# 4_Channel_Relay_Board_Omron.net
KiCad netlist of a schematic drawn in EasyEDA
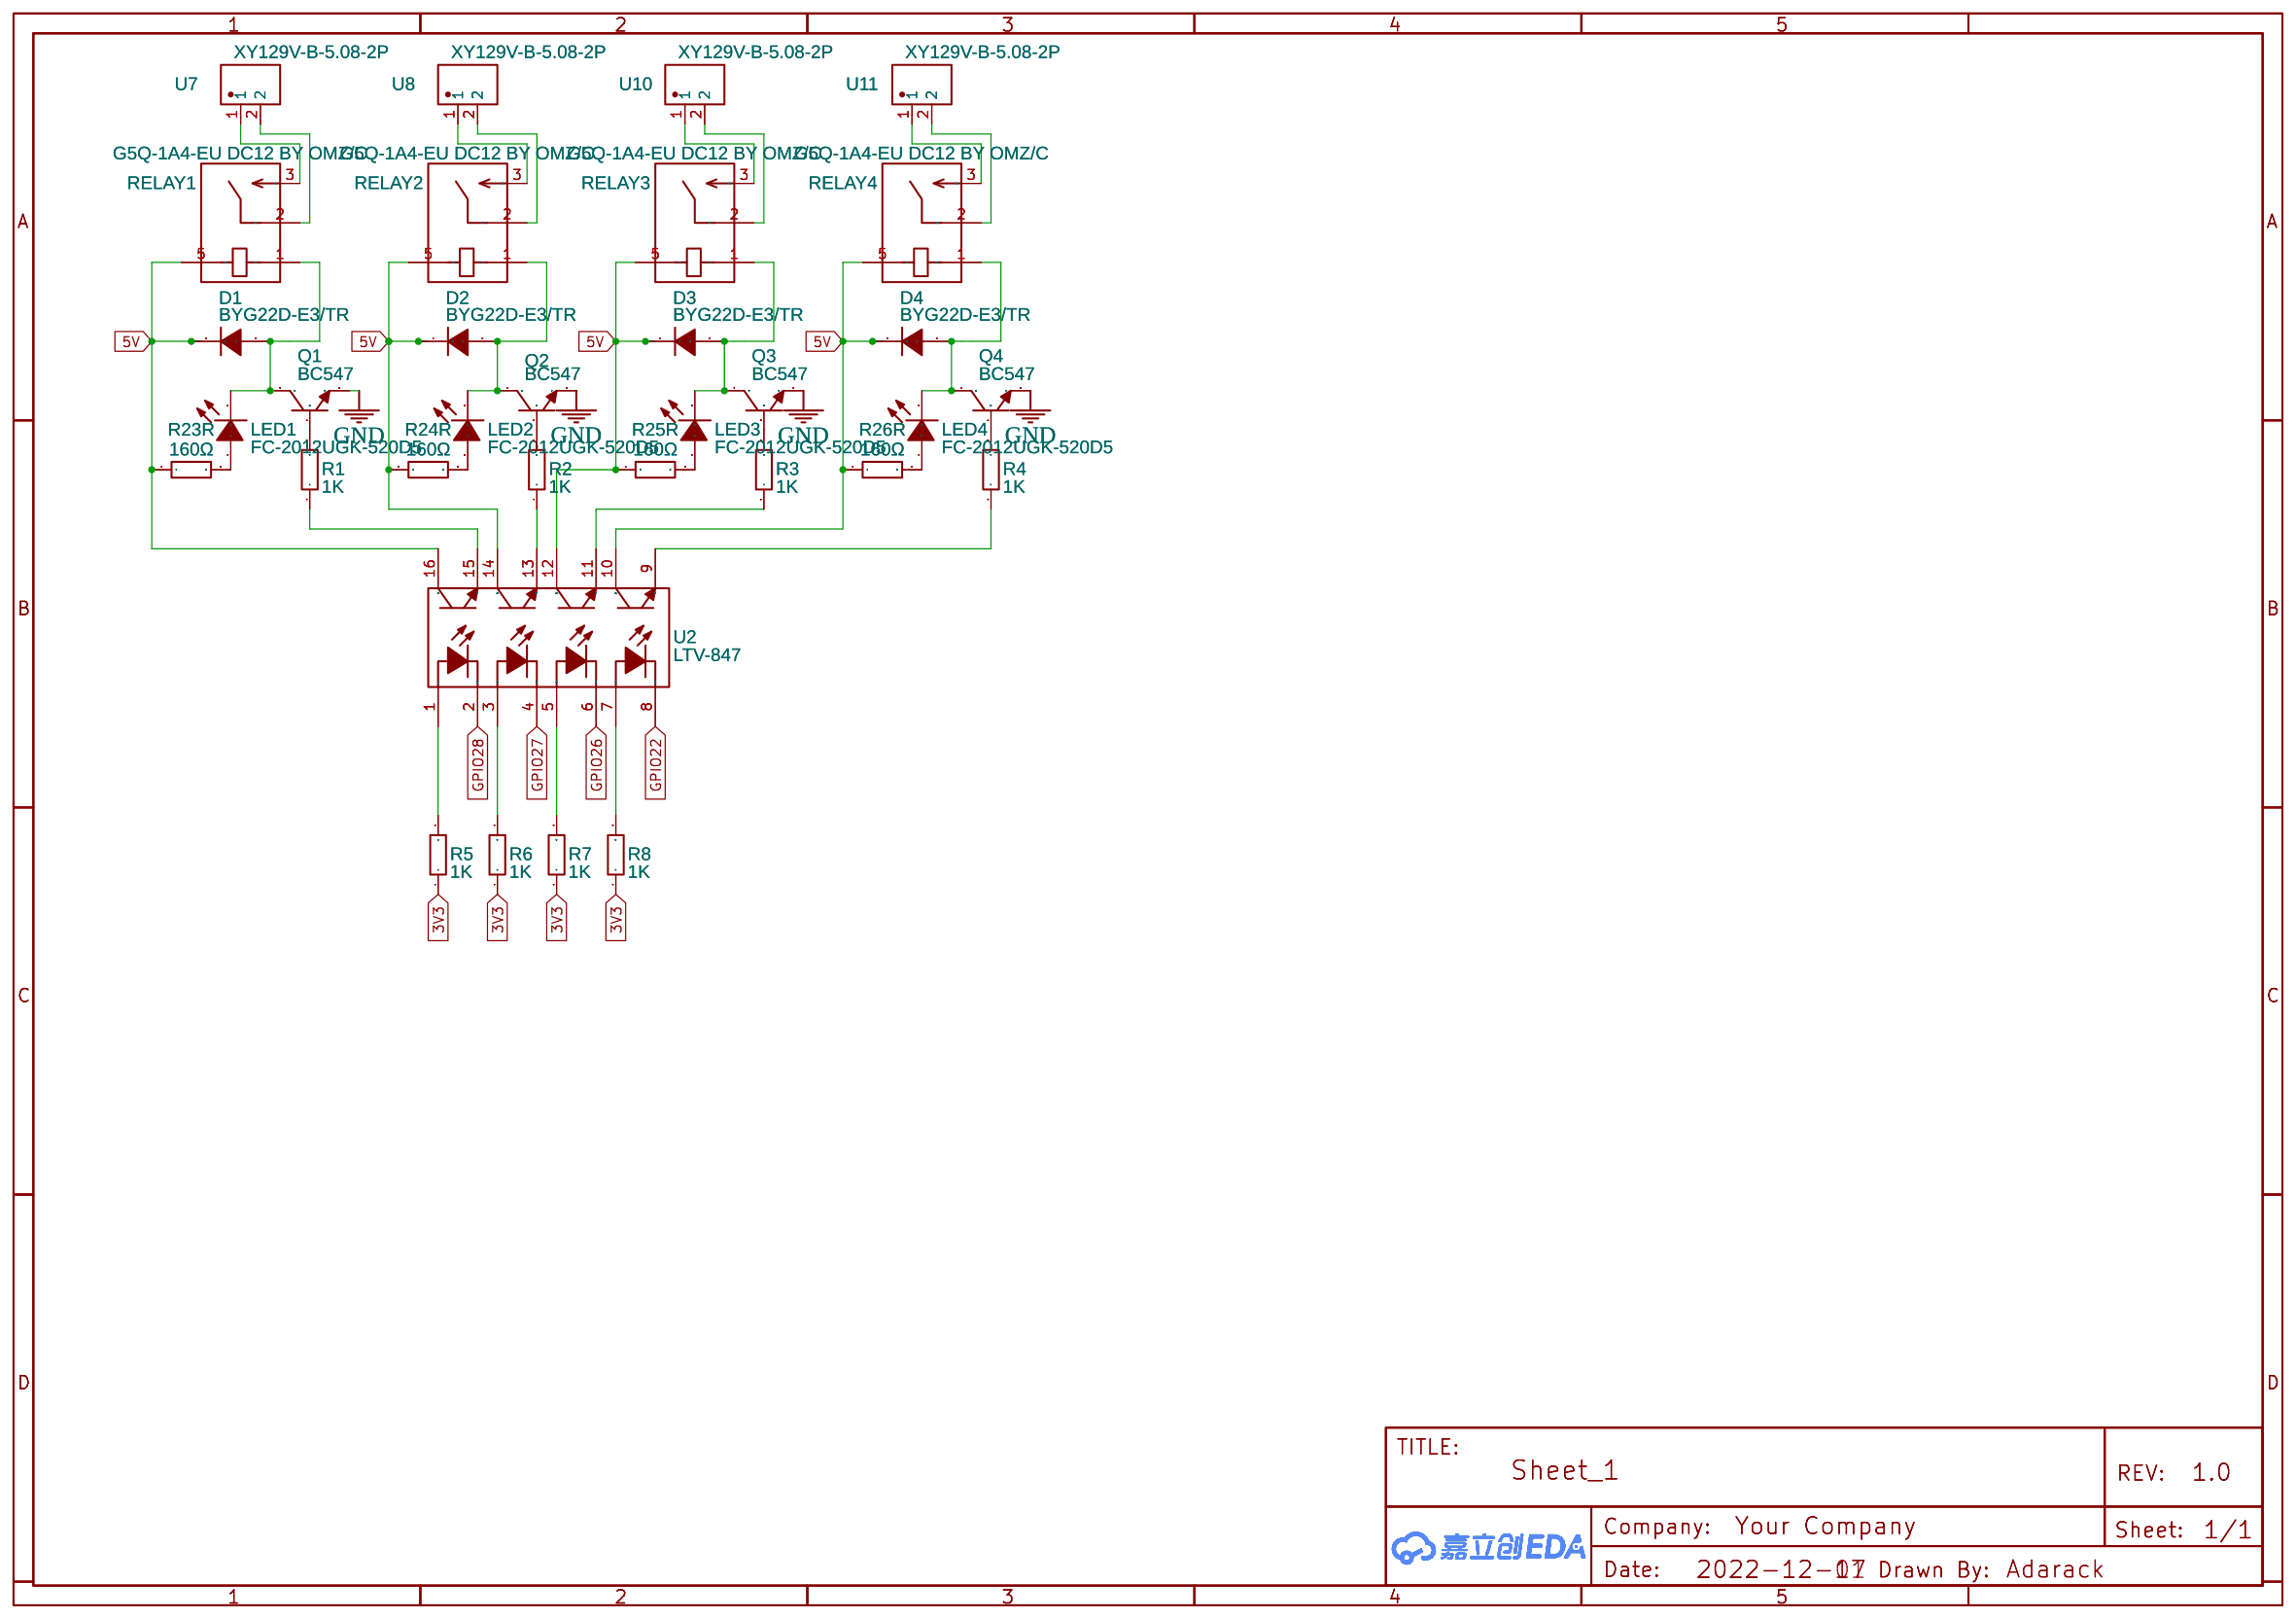
[diagram p0: Relay Section copy]
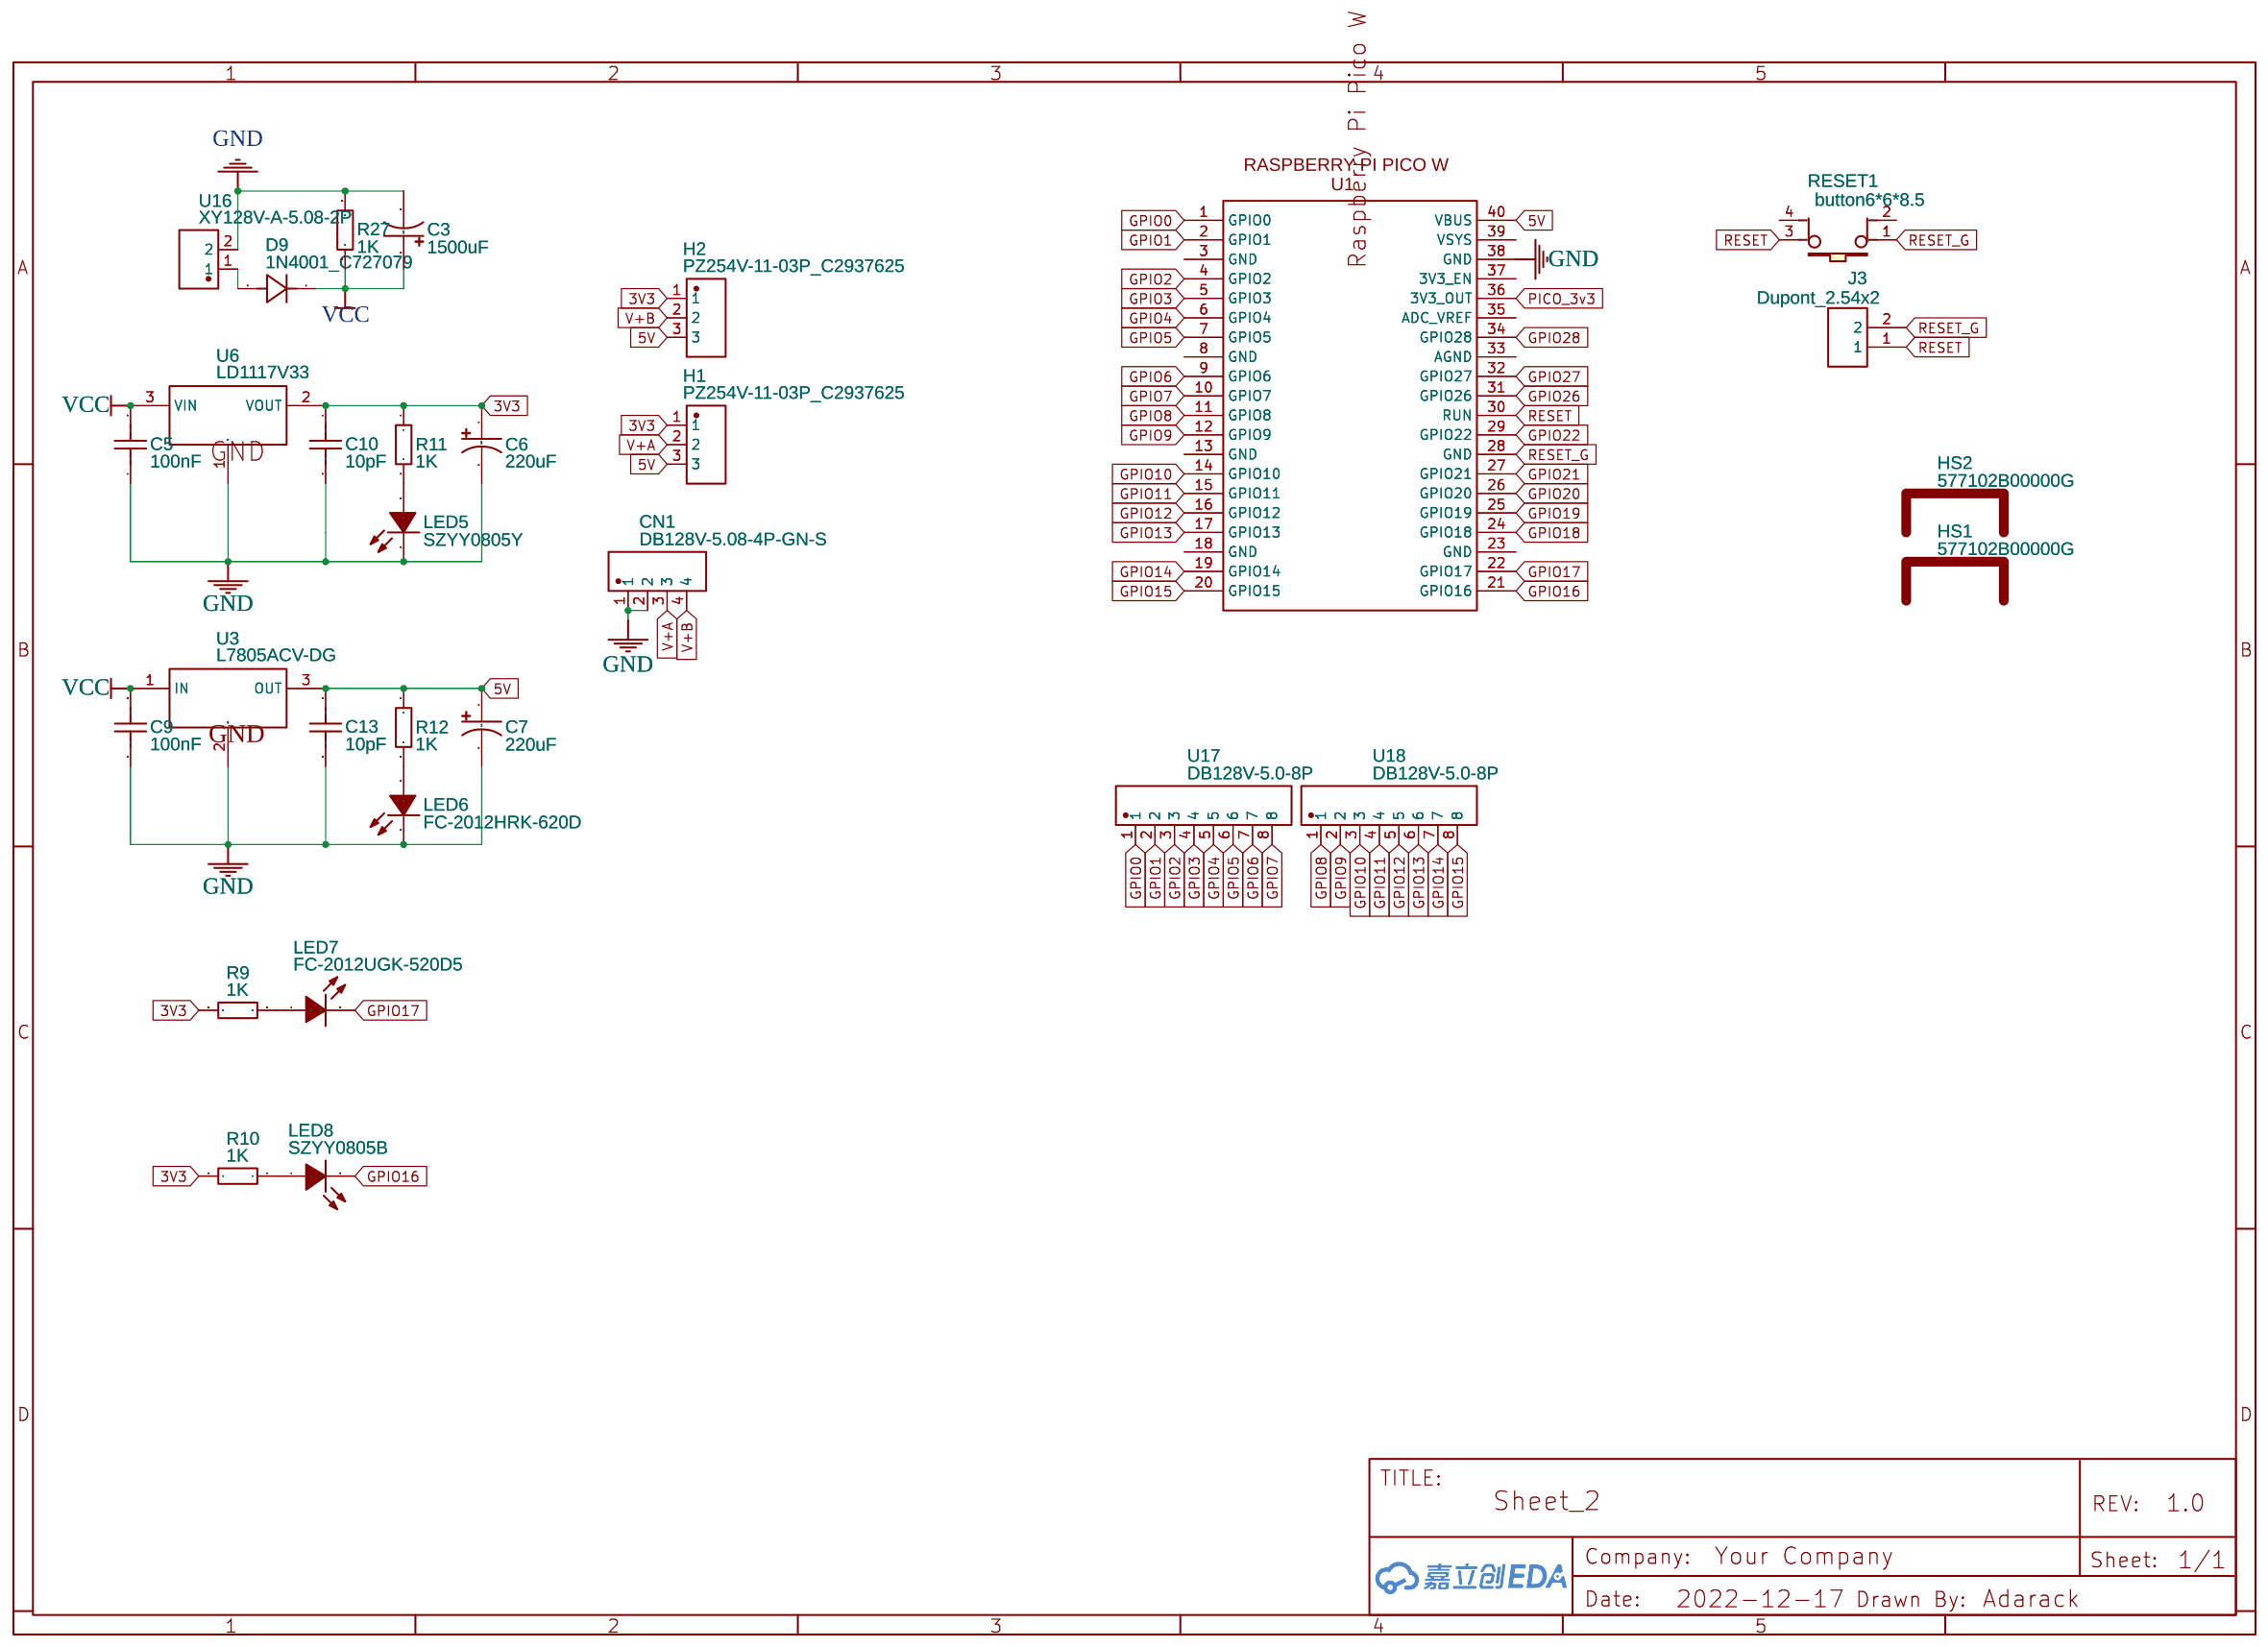
[diagram p1: Pico W Section copy]

(export (version "E")
  (design (tool "Eeschema 10.0.6"))
  (components
    (comp (ref "D1")
      (value "BYG22D-E3/TR")
      (fields (field (name "BOM_Supplier Part") "C52782"))
      (libsource (lib "") (part "BYG22D-E3/TR"))
    )
    (comp (ref "D2")
      (value "BYG22D-E3/TR")
      (fields (field (name "BOM_Supplier Part") "C52782"))
      (libsource (lib "") (part "BYG22D-E3/TR"))
    )
    (comp (ref "D3")
      (value "BYG22D-E3/TR")
      (fields (field (name "BOM_Supplier Part") "C52782"))
      (libsource (lib "") (part "BYG22D-E3/TR"))
    )
    (comp (ref "D4")
      (value "BYG22D-E3/TR")
      (fields (field (name "BOM_Supplier Part") "C52782"))
      (libsource (lib "") (part "BYG22D-E3/TR"))
    )
    (comp (ref "LED1")
      (value "FC-2012UGK-520D5")
      (fields (field (name "BOM_Manufacturer Part") "NCD0805G1") (field (name "BOM_Supplier Part") "C84260"))
      (libsource (lib "") (part "FC-2012UGK-520D5"))
    )
    (comp (ref "LED2")
      (value "FC-2012UGK-520D5")
      (fields (field (name "BOM_Manufacturer Part") "NCD0805G1") (field (name "BOM_Supplier Part") "C84260"))
      (libsource (lib "") (part "FC-2012UGK-520D5"))
    )
    (comp (ref "LED3")
      (value "FC-2012UGK-520D5")
      (fields (field (name "BOM_Manufacturer Part") "NCD0805G1") (field (name "BOM_Supplier Part") "C84260"))
      (libsource (lib "") (part "FC-2012UGK-520D5"))
    )
    (comp (ref "LED4")
      (value "FC-2012UGK-520D5")
      (fields (field (name "BOM_Manufacturer Part") "NCD0805G1") (field (name "BOM_Supplier Part") "C84260"))
      (libsource (lib "") (part "FC-2012UGK-520D5"))
    )
    (comp (ref "Q1")
      (value "BC547")
      (fields (field (name "BOM_Supplier Part") "C2910381"))
      (libsource (lib "") (part "BC547"))
    )
    (comp (ref "Q2")
      (value "BC547")
      (fields (field (name "BOM_Supplier Part") "C2910381"))
      (libsource (lib "") (part "BC547"))
    )
    (comp (ref "Q3")
      (value "BC547")
      (fields (field (name "BOM_Supplier Part") "C2910381"))
      (libsource (lib "") (part "BC547"))
    )
    (comp (ref "Q4")
      (value "BC547")
      (fields (field (name "BOM_Supplier Part") "C2910381"))
      (libsource (lib "") (part "BC547"))
    )
    (comp (ref "R1")
      (value "1K")
      (fields
        (field (name "BOM_Manufacturer Part") "RC0805FR-071KL")
        (field (name "BOM_Supplier Part") "C95781")
      )
      (libsource (lib "") (part "RC0805FR-071KL"))
    )
    (comp (ref "R2")
      (value "1K")
      (fields
        (field (name "BOM_Manufacturer Part") "RC0805FR-071KL")
        (field (name "BOM_Supplier Part") "C95781")
      )
      (libsource (lib "") (part "RC0805FR-071KL"))
    )
    (comp (ref "R3")
      (value "1K")
      (fields
        (field (name "BOM_Manufacturer Part") "RC0805FR-071KL")
        (field (name "BOM_Supplier Part") "C95781")
      )
      (libsource (lib "") (part "RC0805FR-071KL"))
    )
    (comp (ref "R4")
      (value "1K")
      (fields
        (field (name "BOM_Manufacturer Part") "RC0805FR-071KL")
        (field (name "BOM_Supplier Part") "C95781")
      )
      (libsource (lib "") (part "RC0805FR-071KL"))
    )
    (comp (ref "R5")
      (value "1K")
      (fields
        (field (name "BOM_Manufacturer Part") "RC0805FR-071KL")
        (field (name "BOM_Supplier Part") "C95781")
      )
      (libsource (lib "") (part "RC0805FR-071KL"))
    )
    (comp (ref "R6")
      (value "1K")
      (fields
        (field (name "BOM_Manufacturer Part") "RC0805FR-071KL")
        (field (name "BOM_Supplier Part") "C95781")
      )
      (libsource (lib "") (part "RC0805FR-071KL"))
    )
    (comp (ref "R7")
      (value "1K")
      (fields
        (field (name "BOM_Manufacturer Part") "RC0805FR-071KL")
        (field (name "BOM_Supplier Part") "C95781")
      )
      (libsource (lib "") (part "RC0805FR-071KL"))
    )
    (comp (ref "R8")
      (value "1K")
      (fields
        (field (name "BOM_Manufacturer Part") "RC0805FR-071KL")
        (field (name "BOM_Supplier Part") "C95781")
      )
      (libsource (lib "") (part "RC0805FR-071KL"))
    )
    (comp (ref "R23R")
      (value "160Ω")
      (fields
        (field (name "BOM_Manufacturer Part") "0805W8F1600T5E")
        (field (name "BOM_Supplier Part") "C25269")
      )
      (libsource (lib "") (part "0805W8F1600T5E"))
    )
    (comp (ref "R24R")
      (value "160Ω")
      (fields
        (field (name "BOM_Manufacturer Part") "0805W8F1600T5E")
        (field (name "BOM_Supplier Part") "C25269")
      )
      (libsource (lib "") (part "0805W8F1600T5E_1"))
    )
    (comp (ref "R25R")
      (value "160Ω")
      (fields
        (field (name "BOM_Manufacturer Part") "0805W8F1600T5E")
        (field (name "BOM_Supplier Part") "C25269")
      )
      (libsource (lib "") (part "0805W8F1600T5E_3"))
    )
    (comp (ref "R26R")
      (value "160Ω")
      (fields
        (field (name "BOM_Manufacturer Part") "0805W8F1600T5E")
        (field (name "BOM_Supplier Part") "C25269")
      )
      (libsource (lib "") (part "0805W8F1600T5E_2"))
    )
    (comp (ref "RELAY1")
      (value "G5Q-1A4-EU DC12 BY OMZ/C")
      (fields (field (name "BOM_Supplier Part") "C726027"))
      (libsource (lib "") (part "G5Q-1A4-EU DC12 BY OMZ/C"))
    )
    (comp (ref "RELAY2")
      (value "G5Q-1A4-EU DC12 BY OMZ/C")
      (fields (field (name "BOM_Supplier Part") "C726027"))
      (libsource (lib "") (part "G5Q-1A4-EU DC12 BY OMZ/C"))
    )
    (comp (ref "RELAY3")
      (value "G5Q-1A4-EU DC12 BY OMZ/C")
      (fields (field (name "BOM_Supplier Part") "C726027"))
      (libsource (lib "") (part "G5Q-1A4-EU DC12 BY OMZ/C"))
    )
    (comp (ref "RELAY4")
      (value "G5Q-1A4-EU DC12 BY OMZ/C")
      (fields (field (name "BOM_Supplier Part") "C726027"))
      (libsource (lib "") (part "G5Q-1A4-EU DC12 BY OMZ/C"))
    )
    (comp (ref "U2")
      (value "LTV-847")
      (fields (field (name "BOM_Supplier Part") "C10794"))
      (libsource (lib "") (part "LTV-847"))
    )
    (comp (ref "U7")
      (value "XY129V-B-5.08-2P")
      (fields (field (name "BOM_Supplier Part") "C557671"))
      (libsource (lib "") (part "XY129V-B-5.08-2P"))
    )
    (comp (ref "U8")
      (value "XY129V-B-5.08-2P")
      (fields (field (name "BOM_Supplier Part") "C557671"))
      (libsource (lib "") (part "XY129V-B-5.08-2P"))
    )
    (comp (ref "U10")
      (value "XY129V-B-5.08-2P")
      (fields (field (name "BOM_Supplier Part") "C557671"))
      (libsource (lib "") (part "XY129V-B-5.08-2P"))
    )
    (comp (ref "U11")
      (value "XY129V-B-5.08-2P")
      (fields (field (name "BOM_Supplier Part") "C557671"))
      (libsource (lib "") (part "XY129V-B-5.08-2P"))
    )
    (comp (ref "C3")
      (value "1500uF")
      (fields
        (field (name "BOM_Manufacturer Part") "EGF158M1VI25RRSHP")
        (field (name "BOM_Supplier Part") "C238296")
      )
      (libsource (lib "") (part "EGF158M1VI25RRSHP"))
    )
    (comp (ref "C5")
      (value "100nF")
      (fields
        (field (name "BOM_Manufacturer Part") "CC0805KRX7R8BB104")
        (field (name "BOM_Supplier Part") "C519981")
      )
      (libsource (lib "") (part "CC0805KRX7R8BB104"))
    )
    (comp (ref "C6")
      (value "220uF")
      (fields
        (field (name "BOM_Manufacturer Part") "EEUFS0J221")
        (field (name "BOM_Supplier Part") "C407962")
      )
      (libsource (lib "") (part "EEUFS0J221"))
    )
    (comp (ref "C7")
      (value "220uF")
      (fields
        (field (name "BOM_Manufacturer Part") "EEUFS0J221")
        (field (name "BOM_Supplier Part") "C407962")
      )
      (libsource (lib "") (part "EEUFS0J221"))
    )
    (comp (ref "C9")
      (value "100nF")
      (fields
        (field (name "BOM_Manufacturer Part") "CC0805KRX7R8BB104")
        (field (name "BOM_Supplier Part") "C519981")
      )
      (libsource (lib "") (part "CC0805KRX7R8BB104"))
    )
    (comp (ref "C10")
      (value "10pF")
      (fields
        (field (name "BOM_Manufacturer Part") "0805CG100J500NT")
        (field (name "BOM_Supplier Part") "C157608")
      )
      (libsource (lib "") (part "0805CG100J500NT"))
    )
    (comp (ref "C13")
      (value "10pF")
      (fields
        (field (name "BOM_Manufacturer Part") "0805CG100J500NT")
        (field (name "BOM_Supplier Part") "C157608")
      )
      (libsource (lib "") (part "0805CG100J500NT"))
    )
    (comp (ref "CN1")
      (value "DB128V-5.08-4P-GN-S")
      (fields (field (name "BOM_Supplier Part") "C2915641"))
      (libsource (lib "") (part "DB128V-5.08-4P-GN-S"))
    )
    (comp (ref "D9")
      (value "1N4001_C727079")
      (fields (field (name "BOM_Manufacturer Part") "1N4001") (field (name "BOM_Supplier Part") "C727079"))
      (libsource (lib "") (part "1N4001_C727079"))
    )
    (comp (ref "H1")
      (value "PZ254V-11-03P_C2937625")
      (fields
        (field (name "BOM_Manufacturer Part") "PZ254V-11-03P")
        (field (name "BOM_Supplier Part") "C2937625")
      )
      (libsource (lib "") (part "PZ254V-11-03P_C2937625"))
    )
    (comp (ref "H2")
      (value "PZ254V-11-03P_C2937625")
      (fields
        (field (name "BOM_Manufacturer Part") "PZ254V-11-03P")
        (field (name "BOM_Supplier Part") "C2937625")
      )
      (libsource (lib "") (part "PZ254V-11-03P_C2937625"))
    )
    (comp (ref "HS1")
      (value "577102B00000G")
      (fields (field (name "BOM_Supplier Part") "532-577102B00"))
      (libsource (lib "") (part "577102B00000G"))
    )
    (comp (ref "HS2")
      (value "577102B00000G")
      (fields (field (name "BOM_Supplier Part") "532-577102B00"))
      (libsource (lib "") (part "577102B00000G"))
    )
    (comp (ref "J3") (value "Dupont_2.54x2") (libsource (lib "") (part "Dupont_2.54x2")))
    (comp (ref "LED5")
      (value "SZYY0805Y")
      (fields (field (name "BOM_Supplier Part") "C434436"))
      (libsource (lib "") (part "SZYY0805Y"))
    )
    (comp (ref "LED6")
      (value "FC-2012HRK-620D")
      (fields (field (name "BOM_Supplier Part") "C84256"))
      (libsource (lib "") (part "FC-2012HRK-620D"))
    )
    (comp (ref "LED7")
      (value "FC-2012UGK-520D5")
      (fields (field (name "BOM_Manufacturer Part") "NCD0805G1") (field (name "BOM_Supplier Part") "C84260"))
      (libsource (lib "") (part "FC-2012UGK-520D5"))
    )
    (comp (ref "LED8")
      (value "SZYY0805B")
      (fields (field (name "BOM_Supplier Part") "C434433"))
      (libsource (lib "") (part "SZYY0805B"))
    )
    (comp (ref "R9")
      (value "1K")
      (fields
        (field (name "BOM_Manufacturer Part") "RC0805FR-071KL")
        (field (name "BOM_Supplier Part") "C95781")
      )
      (libsource (lib "") (part "RC0805FR-071KL"))
    )
    (comp (ref "R10")
      (value "1K")
      (fields
        (field (name "BOM_Manufacturer Part") "RC0805FR-071KL")
        (field (name "BOM_Supplier Part") "C95781")
      )
      (libsource (lib "") (part "RC0805FR-071KL"))
    )
    (comp (ref "R11")
      (value "1K")
      (fields
        (field (name "BOM_Manufacturer Part") "RC0805FR-071KL")
        (field (name "BOM_Supplier Part") "C95781")
      )
      (libsource (lib "") (part "RC0805FR-071KL_1"))
    )
    (comp (ref "R12")
      (value "1K")
      (fields
        (field (name "BOM_Manufacturer Part") "RC0805FR-071KL")
        (field (name "BOM_Supplier Part") "C95781")
      )
      (libsource (lib "") (part "RC0805FR-071KL_1"))
    )
    (comp (ref "R27")
      (value "1K")
      (fields
        (field (name "BOM_Manufacturer Part") "RC0805FR-071KL")
        (field (name "BOM_Supplier Part") "C95781")
      )
      (libsource (lib "") (part "RC0805FR-071KL_2"))
    )
    (comp (ref "RESET1")
      (value "button6*6*8.5")
      (fields (field (name "BOM_Supplier Part") "C59980"))
      (libsource (lib "") (part "button6*6*8.5"))
    )
    (comp (ref "U3")
      (value "L7805ACV-DG")
      (fields (field (name "BOM_Supplier Part") "C472632"))
      (libsource (lib "") (part "L7805ACV-DG"))
    )
    (comp (ref "U6")
      (value "LD1117V33")
      (fields (field (name "BOM_Supplier Part") "C283467"))
      (libsource (lib "") (part "LD1117V33"))
    )
    (comp (ref "U9") (value "Raspberry Pi Pico W") (libsource (lib "") (part "Raspberry Pi Pico W")))
    (comp (ref "U16")
      (value "XY128V-A-5.08-2P")
      (fields (field (name "BOM_Supplier Part") "C557665"))
      (libsource (lib "") (part "XY128V-A-5.08-2P"))
    )
    (comp (ref "U17")
      (value "DB128V-5.0-8P")
      (fields (field (name "BOM_Supplier Part") "C395863"))
      (libsource (lib "") (part "DB128V-5.0-8P"))
    )
    (comp (ref "U18")
      (value "DB128V-5.0-8P")
      (fields (field (name "BOM_Supplier Part") "C395863"))
      (libsource (lib "") (part "DB128V-5.0-8P"))
    )
  )
  (nets
    (net (code "1") (name "3V3") (class "Default")
      (node (ref "C10") (pin "1") (pinfunction "1_1") (pintype "unspecified"))
      (node (ref "C6") (pin "1") (pinfunction "1_1") (pintype "unspecified"))
      (node (ref "H1") (pin "1") (pinfunction "1_1") (pintype "unspecified"))
      (node (ref "H2") (pin "1") (pinfunction "1_1") (pintype "unspecified"))
      (node (ref "R10") (pin "2") (pinfunction "2_2") (pintype "input"))
      (node (ref "R11") (pin "1") (pinfunction "1_1") (pintype "input"))
      (node (ref "R5") (pin "1") (pinfunction "1_1") (pintype "input"))
      (node (ref "R6") (pin "1") (pinfunction "1_1") (pintype "input"))
      (node (ref "R7") (pin "1") (pinfunction "1_1") (pintype "input"))
      (node (ref "R8") (pin "1") (pinfunction "1_1") (pintype "input"))
      (node (ref "R9") (pin "2") (pinfunction "2_2") (pintype "input"))
      (node (ref "U6") (pin "2") (pinfunction "VOUT_2") (pintype "passive"))
    )
    (net (code "2") (name "5V") (class "Default")
      (node (ref "C13") (pin "1") (pinfunction "1_1") (pintype "unspecified"))
      (node (ref "C7") (pin "1") (pinfunction "1_1") (pintype "unspecified"))
      (node (ref "D1") (pin "1") (pinfunction "K_1") (pintype "unspecified"))
      (node (ref "D2") (pin "1") (pinfunction "K_1") (pintype "unspecified"))
      (node (ref "D3") (pin "1") (pinfunction "K_1") (pintype "unspecified"))
      (node (ref "D4") (pin "1") (pinfunction "K_1") (pintype "unspecified"))
      (node (ref "H1") (pin "3") (pinfunction "3_3") (pintype "unspecified"))
      (node (ref "H2") (pin "3") (pinfunction "3_3") (pintype "unspecified"))
      (node (ref "R12") (pin "1") (pinfunction "1_1") (pintype "input"))
      (node (ref "R23R") (pin "1") (pinfunction "1_1") (pintype "input"))
      (node (ref "R24R") (pin "1") (pinfunction "1_1") (pintype "input"))
      (node (ref "R25R") (pin "1") (pinfunction "1_1") (pintype "input"))
      (node (ref "R26R") (pin "1") (pinfunction "1_1") (pintype "input"))
      (node (ref "RELAY1") (pin "5") (pinfunction "5_5") (pintype "unspecified"))
      (node (ref "RELAY2") (pin "5") (pinfunction "5_5") (pintype "unspecified"))
      (node (ref "RELAY3") (pin "5") (pinfunction "5_5") (pintype "unspecified"))
      (node (ref "RELAY4") (pin "5") (pinfunction "5_5") (pintype "unspecified"))
      (node (ref "U2") (pin "10") (pinfunction "COL_10") (pintype "unspecified"))
      (node (ref "U2") (pin "12") (pinfunction "COL_12") (pintype "unspecified"))
      (node (ref "U2") (pin "14") (pinfunction "COL_14") (pintype "unspecified"))
      (node (ref "U2") (pin "16") (pinfunction "COL_16") (pintype "unspecified"))
      (node (ref "U3") (pin "3") (pinfunction "OUT_3") (pintype "passive"))
      (node (ref "U9") (pin "40") (pinfunction "VBUS_40") (pintype "unspecified"))
    )
    (net (code "3") (name "GND") (class "Default")
      (node (ref "C10") (pin "2") (pinfunction "2_2") (pintype "unspecified"))
      (node (ref "C13") (pin "2") (pinfunction "2_2") (pintype "unspecified"))
      (node (ref "C3") (pin "2") (pinfunction "2_2") (pintype "unspecified"))
      (node (ref "C5") (pin "1") (pinfunction "1_1") (pintype "unspecified"))
      (node (ref "C6") (pin "2") (pinfunction "2_2") (pintype "unspecified"))
      (node (ref "C7") (pin "2") (pinfunction "2_2") (pintype "unspecified"))
      (node (ref "C9") (pin "1") (pinfunction "1_1") (pintype "unspecified"))
      (node (ref "CN1") (pin "1") (pinfunction "1_1") (pintype "unspecified"))
      (node (ref "CN1") (pin "2") (pinfunction "2_2") (pintype "unspecified"))
      (node (ref "LED5") (pin "1") (pinfunction "-_1") (pintype "unspecified"))
      (node (ref "LED6") (pin "1") (pinfunction "-_1") (pintype "unspecified"))
      (node (ref "Q1") (pin "3") (pinfunction "E_3") (pintype "unspecified"))
      (node (ref "Q2") (pin "3") (pinfunction "E_3") (pintype "unspecified"))
      (node (ref "Q3") (pin "3") (pinfunction "E_3") (pintype "unspecified"))
      (node (ref "Q4") (pin "3") (pinfunction "E_3") (pintype "unspecified"))
      (node (ref "R27") (pin "2") (pinfunction "2_2") (pintype "input"))
      (node (ref "U16") (pin "2") (pinfunction "2_2") (pintype "unspecified"))
      (node (ref "U3") (pin "2") (pinfunction "GND_2") (pintype "passive"))
      (node (ref "U6") (pin "1") (pinfunction "GND_1") (pintype "unspecified"))
      (node (ref "U9") (pin "38") (pinfunction "GND_38") (pintype "unspecified"))
    )
    (net (code "4") (name "GPIO0") (class "Default")
      (node (ref "U17") (pin "1") (pinfunction "1_1") (pintype "unspecified"))
      (node (ref "U9") (pin "1") (pinfunction "GPIO0_1") (pintype "unspecified"))
    )
    (net (code "5") (name "GPIO1") (class "Default")
      (node (ref "U17") (pin "2") (pinfunction "2_2") (pintype "unspecified"))
      (node (ref "U9") (pin "2") (pinfunction "GPIO1_2") (pintype "unspecified"))
    )
    (net (code "6") (name "GPIO2") (class "Default")
      (node (ref "U17") (pin "3") (pinfunction "3_3") (pintype "unspecified"))
      (node (ref "U9") (pin "4") (pinfunction "GPIO2_4") (pintype "unspecified"))
    )
    (net (code "7") (name "GPIO3") (class "Default")
      (node (ref "U17") (pin "4") (pinfunction "4_4") (pintype "unspecified"))
      (node (ref "U9") (pin "5") (pinfunction "GPIO3_5") (pintype "unspecified"))
    )
    (net (code "8") (name "GPIO4") (class "Default")
      (node (ref "U17") (pin "5") (pinfunction "5_5") (pintype "unspecified"))
      (node (ref "U9") (pin "6") (pinfunction "GPIO4_6") (pintype "unspecified"))
    )
    (net (code "9") (name "GPIO5") (class "Default")
      (node (ref "U17") (pin "6") (pinfunction "6_6") (pintype "unspecified"))
      (node (ref "U9") (pin "7") (pinfunction "GPIO5_7") (pintype "unspecified"))
    )
    (net (code "10") (name "GPIO6") (class "Default")
      (node (ref "U17") (pin "7") (pinfunction "7_7") (pintype "unspecified"))
      (node (ref "U9") (pin "9") (pinfunction "GPIO6_9") (pintype "unspecified"))
    )
    (net (code "11") (name "GPIO7") (class "Default")
      (node (ref "U17") (pin "8") (pinfunction "8_8") (pintype "unspecified"))
      (node (ref "U9") (pin "10") (pinfunction "GPIO7_10") (pintype "unspecified"))
    )
    (net (code "12") (name "GPIO8") (class "Default")
      (node (ref "U18") (pin "1") (pinfunction "1_1") (pintype "unspecified"))
      (node (ref "U9") (pin "11") (pinfunction "GPIO8_11") (pintype "unspecified"))
    )
    (net (code "13") (name "GPIO9") (class "Default")
      (node (ref "U18") (pin "2") (pinfunction "2_2") (pintype "unspecified"))
      (node (ref "U9") (pin "12") (pinfunction "GPIO9_12") (pintype "unspecified"))
    )
    (net (code "14") (name "GPIO10") (class "Default")
      (node (ref "U18") (pin "3") (pinfunction "3_3") (pintype "unspecified"))
      (node (ref "U9") (pin "14") (pinfunction "GPIO10_14") (pintype "unspecified"))
    )
    (net (code "15") (name "GPIO11") (class "Default")
      (node (ref "U18") (pin "4") (pinfunction "4_4") (pintype "unspecified"))
      (node (ref "U9") (pin "15") (pinfunction "GPIO11_15") (pintype "unspecified"))
    )
    (net (code "16") (name "GPIO12") (class "Default")
      (node (ref "U18") (pin "5") (pinfunction "5_5") (pintype "unspecified"))
      (node (ref "U9") (pin "16") (pinfunction "GPIO12_16") (pintype "unspecified"))
    )
    (net (code "17") (name "GPIO13") (class "Default")
      (node (ref "U18") (pin "6") (pinfunction "6_6") (pintype "unspecified"))
      (node (ref "U9") (pin "17") (pinfunction "GPIO13_17") (pintype "unspecified"))
    )
    (net (code "18") (name "GPIO14") (class "Default")
      (node (ref "U18") (pin "7") (pinfunction "7_7") (pintype "unspecified"))
      (node (ref "U9") (pin "19") (pinfunction "GPIO14_19") (pintype "unspecified"))
    )
    (net (code "19") (name "GPIO15") (class "Default")
      (node (ref "U18") (pin "8") (pinfunction "8_8") (pintype "unspecified"))
      (node (ref "U9") (pin "20") (pinfunction "GPIO15_20") (pintype "unspecified"))
    )
    (net (code "20") (name "GPIO16") (class "Default")
      (node (ref "LED8") (pin "2") (pinfunction "-_2") (pintype "unspecified"))
      (node (ref "U9") (pin "21") (pinfunction "GPIO16_21") (pintype "unspecified"))
    )
    (net (code "21") (name "GPIO17") (class "Default")
      (node (ref "LED7") (pin "2") (pinfunction "K_2") (pintype "unspecified"))
      (node (ref "U9") (pin "22") (pinfunction "GPIO17_22") (pintype "unspecified"))
    )
    (net (code "22") (name "GPIO18") (class "Default")
      (node (ref "U9") (pin "24") (pinfunction "GPIO18_24") (pintype "unspecified"))
    )
    (net (code "23") (name "GPIO19") (class "Default")
      (node (ref "U9") (pin "25") (pinfunction "GPIO19_25") (pintype "unspecified"))
    )
    (net (code "24") (name "GPIO20") (class "Default")
      (node (ref "U9") (pin "26") (pinfunction "GPIO20_26") (pintype "unspecified"))
    )
    (net (code "25") (name "GPIO21") (class "Default")
      (node (ref "U9") (pin "27") (pinfunction "GPIO21_27") (pintype "unspecified"))
    )
    (net (code "26") (name "GPIO22") (class "Default")
      (node (ref "U2") (pin "8") (pinfunction "CAT_8") (pintype "unspecified"))
      (node (ref "U9") (pin "29") (pinfunction "GPIO22_29") (pintype "unspecified"))
    )
    (net (code "27") (name "GPIO26") (class "Default")
      (node (ref "U2") (pin "6") (pinfunction "CAT_6") (pintype "unspecified"))
      (node (ref "U9") (pin "31") (pinfunction "GPIO26_31") (pintype "unspecified"))
    )
    (net (code "28") (name "GPIO27") (class "Default")
      (node (ref "U2") (pin "4") (pinfunction "CAT_4") (pintype "unspecified"))
      (node (ref "U9") (pin "32") (pinfunction "GPIO27_32") (pintype "unspecified"))
    )
    (net (code "29") (name "GPIO28") (class "Default")
      (node (ref "U2") (pin "2") (pinfunction "CAT_2") (pintype "unspecified"))
      (node (ref "U9") (pin "34") (pinfunction "GPIO28_34") (pintype "unspecified"))
    )
    (net (code "30") (name "Net-(D1-A)") (class "Default")
      (node (ref "D1") (pin "2") (pinfunction "A_2") (pintype "unspecified"))
      (node (ref "LED1") (pin "2") (pinfunction "K_2") (pintype "unspecified"))
      (node (ref "Q1") (pin "1") (pinfunction "C_1") (pintype "unspecified"))
      (node (ref "RELAY1") (pin "1") (pinfunction "1_1") (pintype "unspecified"))
    )
    (net (code "31") (name "Net-(D2-A)") (class "Default")
      (node (ref "D2") (pin "2") (pinfunction "A_2") (pintype "unspecified"))
      (node (ref "LED2") (pin "2") (pinfunction "K_2") (pintype "unspecified"))
      (node (ref "Q2") (pin "1") (pinfunction "C_1") (pintype "unspecified"))
      (node (ref "RELAY2") (pin "1") (pinfunction "1_1") (pintype "unspecified"))
    )
    (net (code "32") (name "Net-(D3-A)") (class "Default")
      (node (ref "D3") (pin "2") (pinfunction "A_2") (pintype "unspecified"))
      (node (ref "LED3") (pin "2") (pinfunction "K_2") (pintype "unspecified"))
      (node (ref "Q3") (pin "1") (pinfunction "C_1") (pintype "unspecified"))
      (node (ref "RELAY3") (pin "1") (pinfunction "1_1") (pintype "unspecified"))
    )
    (net (code "33") (name "Net-(D4-A)") (class "Default")
      (node (ref "D4") (pin "2") (pinfunction "A_2") (pintype "unspecified"))
      (node (ref "LED4") (pin "2") (pinfunction "K_2") (pintype "unspecified"))
      (node (ref "Q4") (pin "1") (pinfunction "C_1") (pintype "unspecified"))
      (node (ref "RELAY4") (pin "1") (pinfunction "1_1") (pintype "unspecified"))
    )
    (net (code "34") (name "Net-(D9-A)") (class "Default")
      (node (ref "D9") (pin "2") (pinfunction "A_2") (pintype "unspecified"))
      (node (ref "U16") (pin "1") (pinfunction "1_1") (pintype "unspecified"))
    )
    (net (code "35") (name "Net-(LED1-A)") (class "Default")
      (node (ref "LED1") (pin "1") (pinfunction "A_1") (pintype "unspecified"))
      (node (ref "R23R") (pin "2") (pinfunction "2_2") (pintype "input"))
    )
    (net (code "36") (name "Net-(LED2-A)") (class "Default")
      (node (ref "LED2") (pin "1") (pinfunction "A_1") (pintype "unspecified"))
      (node (ref "R24R") (pin "2") (pinfunction "2_2") (pintype "input"))
    )
    (net (code "37") (name "Net-(LED3-A)") (class "Default")
      (node (ref "LED3") (pin "1") (pinfunction "A_1") (pintype "unspecified"))
      (node (ref "R25R") (pin "2") (pinfunction "2_2") (pintype "input"))
    )
    (net (code "38") (name "Net-(LED4-A)") (class "Default")
      (node (ref "LED4") (pin "1") (pinfunction "A_1") (pintype "unspecified"))
      (node (ref "R26R") (pin "2") (pinfunction "2_2") (pintype "input"))
    )
    (net (code "39") (name "Net-(LED5-+)") (class "Default")
      (node (ref "LED5") (pin "2") (pinfunction "+_2") (pintype "unspecified"))
      (node (ref "R11") (pin "2") (pinfunction "2_2") (pintype "input"))
    )
    (net (code "40") (name "Net-(LED6-+)") (class "Default")
      (node (ref "LED6") (pin "2") (pinfunction "+_2") (pintype "unspecified"))
      (node (ref "R12") (pin "2") (pinfunction "2_2") (pintype "input"))
    )
    (net (code "41") (name "Net-(LED7-A)") (class "Default")
      (node (ref "LED7") (pin "1") (pinfunction "A_1") (pintype "unspecified"))
      (node (ref "R9") (pin "1") (pinfunction "1_1") (pintype "input"))
    )
    (net (code "42") (name "Net-(LED8-+)") (class "Default")
      (node (ref "LED8") (pin "1") (pinfunction "+_1") (pintype "unspecified"))
      (node (ref "R10") (pin "1") (pinfunction "1_1") (pintype "input"))
    )
    (net (code "43") (name "Net-(Q1-B)") (class "Default")
      (node (ref "Q1") (pin "2") (pinfunction "B_2") (pintype "unspecified"))
      (node (ref "R1") (pin "2") (pinfunction "2_2") (pintype "input"))
    )
    (net (code "44") (name "Net-(Q2-B)") (class "Default")
      (node (ref "Q2") (pin "2") (pinfunction "B_2") (pintype "unspecified"))
      (node (ref "R2") (pin "2") (pinfunction "2_2") (pintype "input"))
    )
    (net (code "45") (name "Net-(Q3-B)") (class "Default")
      (node (ref "Q3") (pin "2") (pinfunction "B_2") (pintype "unspecified"))
      (node (ref "R3") (pin "2") (pinfunction "2_2") (pintype "input"))
    )
    (net (code "46") (name "Net-(Q4-B)") (class "Default")
      (node (ref "Q4") (pin "2") (pinfunction "B_2") (pintype "unspecified"))
      (node (ref "R4") (pin "2") (pinfunction "2_2") (pintype "input"))
    )
    (net (code "47") (name "Net-(R1-Pad1)") (class "Default")
      (node (ref "R1") (pin "1") (pinfunction "1_1") (pintype "input"))
      (node (ref "U2") (pin "15") (pinfunction "EM_15") (pintype "unspecified"))
    )
    (net (code "48") (name "Net-(R2-Pad1)") (class "Default")
      (node (ref "R2") (pin "1") (pinfunction "1_1") (pintype "input"))
      (node (ref "U2") (pin "13") (pinfunction "EM_13") (pintype "unspecified"))
    )
    (net (code "49") (name "Net-(R3-Pad1)") (class "Default")
      (node (ref "R3") (pin "1") (pinfunction "1_1") (pintype "input"))
      (node (ref "U2") (pin "11") (pinfunction "EM_11") (pintype "unspecified"))
    )
    (net (code "50") (name "Net-(R4-Pad1)") (class "Default")
      (node (ref "R4") (pin "1") (pinfunction "1_1") (pintype "input"))
      (node (ref "U2") (pin "9") (pinfunction "EM_9") (pintype "unspecified"))
    )
    (net (code "51") (name "Net-(R5-Pad2)") (class "Default")
      (node (ref "R5") (pin "2") (pinfunction "2_2") (pintype "input"))
      (node (ref "U2") (pin "1") (pinfunction "AN_1") (pintype "unspecified"))
    )
    (net (code "52") (name "Net-(R6-Pad2)") (class "Default")
      (node (ref "R6") (pin "2") (pinfunction "2_2") (pintype "input"))
      (node (ref "U2") (pin "3") (pinfunction "AN_3") (pintype "unspecified"))
    )
    (net (code "53") (name "Net-(R7-Pad2)") (class "Default")
      (node (ref "R7") (pin "2") (pinfunction "2_2") (pintype "input"))
      (node (ref "U2") (pin "5") (pinfunction "AN_5") (pintype "unspecified"))
    )
    (net (code "54") (name "Net-(R8-Pad2)") (class "Default")
      (node (ref "R8") (pin "2") (pinfunction "2_2") (pintype "input"))
      (node (ref "U2") (pin "7") (pinfunction "AN_7") (pintype "unspecified"))
    )
    (net (code "55") (name "Net-(RELAY1-Pad2)") (class "Default")
      (node (ref "RELAY1") (pin "2") (pinfunction "2_2") (pintype "unspecified"))
      (node (ref "U7") (pin "2") (pinfunction "2_2") (pintype "unspecified"))
    )
    (net (code "56") (name "Net-(RELAY1-Pad3)") (class "Default")
      (node (ref "RELAY1") (pin "3") (pinfunction "3_3") (pintype "unspecified"))
      (node (ref "U7") (pin "1") (pinfunction "1_1") (pintype "unspecified"))
    )
    (net (code "57") (name "Net-(RELAY2-Pad2)") (class "Default")
      (node (ref "RELAY2") (pin "2") (pinfunction "2_2") (pintype "unspecified"))
      (node (ref "U8") (pin "2") (pinfunction "2_2") (pintype "unspecified"))
    )
    (net (code "58") (name "Net-(RELAY2-Pad3)") (class "Default")
      (node (ref "RELAY2") (pin "3") (pinfunction "3_3") (pintype "unspecified"))
      (node (ref "U8") (pin "1") (pinfunction "1_1") (pintype "unspecified"))
    )
    (net (code "59") (name "Net-(RELAY3-Pad2)") (class "Default")
      (node (ref "RELAY3") (pin "2") (pinfunction "2_2") (pintype "unspecified"))
      (node (ref "U10") (pin "2") (pinfunction "2_2") (pintype "unspecified"))
    )
    (net (code "60") (name "Net-(RELAY3-Pad3)") (class "Default")
      (node (ref "RELAY3") (pin "3") (pinfunction "3_3") (pintype "unspecified"))
      (node (ref "U10") (pin "1") (pinfunction "1_1") (pintype "unspecified"))
    )
    (net (code "61") (name "Net-(RELAY4-Pad2)") (class "Default")
      (node (ref "RELAY4") (pin "2") (pinfunction "2_2") (pintype "unspecified"))
      (node (ref "U11") (pin "2") (pinfunction "2_2") (pintype "unspecified"))
    )
    (net (code "62") (name "Net-(RELAY4-Pad3)") (class "Default")
      (node (ref "RELAY4") (pin "3") (pinfunction "3_3") (pintype "unspecified"))
      (node (ref "U11") (pin "1") (pinfunction "1_1") (pintype "unspecified"))
    )
    (net (code "63") (name "PICO_3v3") (class "Default")
      (node (ref "U9") (pin "36") (pinfunction "3V3_OUT_36") (pintype "unspecified"))
    )
    (net (code "64") (name "RESET") (class "Default")
      (node (ref "J3") (pin "1") (pinfunction "1_1") (pintype "unspecified"))
      (node (ref "RESET1") (pin "3") (pinfunction "3_3") (pintype "input"))
      (node (ref "U9") (pin "30") (pinfunction "RUN_30") (pintype "unspecified"))
    )
    (net (code "65") (name "RESET_G") (class "Default")
      (node (ref "J3") (pin "2") (pinfunction "2_2") (pintype "unspecified"))
      (node (ref "RESET1") (pin "1") (pinfunction "1_1") (pintype "input"))
      (node (ref "U9") (pin "28") (pinfunction "GND_28") (pintype "unspecified"))
    )
    (net (code "66") (name "V+A") (class "Default")
      (node (ref "CN1") (pin "3") (pinfunction "3_3") (pintype "unspecified"))
      (node (ref "H1") (pin "2") (pinfunction "2_2") (pintype "unspecified"))
    )
    (net (code "67") (name "V+B") (class "Default")
      (node (ref "CN1") (pin "4") (pinfunction "4_4") (pintype "unspecified"))
      (node (ref "H2") (pin "2") (pinfunction "2_2") (pintype "unspecified"))
    )
    (net (code "68") (name "VCC") (class "Default")
      (node (ref "C3") (pin "1") (pinfunction "1_1") (pintype "unspecified"))
      (node (ref "C5") (pin "2") (pinfunction "2_2") (pintype "unspecified"))
      (node (ref "C9") (pin "2") (pinfunction "2_2") (pintype "unspecified"))
      (node (ref "D9") (pin "1") (pinfunction "K_1") (pintype "unspecified"))
      (node (ref "R27") (pin "1") (pinfunction "1_1") (pintype "input"))
      (node (ref "U3") (pin "1") (pinfunction "IN_1") (pintype "passive"))
      (node (ref "U6") (pin "3") (pinfunction "VIN_3") (pintype "passive"))
    )
    (net (code "69") (name "unconnected-(RESET1-Pad2)") (class "Default")
      (node (ref "RESET1") (pin "2") (pinfunction "2_2") (pintype "input"))
    )
    (net (code "70") (name "unconnected-(RESET1-Pad4)") (class "Default")
      (node (ref "RESET1") (pin "4") (pinfunction "4_4") (pintype "input"))
    )
    (net (code "71") (name "unconnected-(U9-3V3_EN-Pad37)") (class "Default")
      (node (ref "U9") (pin "37") (pinfunction "3V3_EN_37") (pintype "unspecified"))
    )
    (net (code "72") (name "unconnected-(U9-ADC_VREF-Pad35)") (class "Default")
      (node (ref "U9") (pin "35") (pinfunction "ADC_VREF_35") (pintype "unspecified"))
    )
    (net (code "73") (name "unconnected-(U9-AGND-Pad33)") (class "Default")
      (node (ref "U9") (pin "33") (pinfunction "AGND_33") (pintype "unspecified"))
    )
    (net (code "74") (name "unconnected-(U9-GND-Pad3)") (class "Default")
      (node (ref "U9") (pin "3") (pinfunction "GND_3") (pintype "unspecified"))
    )
    (net (code "75") (name "unconnected-(U9-GND-Pad8)") (class "Default")
      (node (ref "U9") (pin "8") (pinfunction "GND_8") (pintype "unspecified"))
    )
    (net (code "76") (name "unconnected-(U9-GND-Pad13)") (class "Default")
      (node (ref "U9") (pin "13") (pinfunction "GND_13") (pintype "unspecified"))
    )
    (net (code "77") (name "unconnected-(U9-GND-Pad18)") (class "Default")
      (node (ref "U9") (pin "18") (pinfunction "GND_18") (pintype "unspecified"))
    )
    (net (code "78") (name "unconnected-(U9-GND-Pad23)") (class "Default")
      (node (ref "U9") (pin "23") (pinfunction "GND_23") (pintype "unspecified"))
    )
    (net (code "79") (name "unconnected-(U9-VSYS-Pad39)") (class "Default")
      (node (ref "U9") (pin "39") (pinfunction "VSYS_39") (pintype "unspecified"))
    )
  )
)
